# V_4.net
KiCad netlist of a schematic drawn in Altium Designer
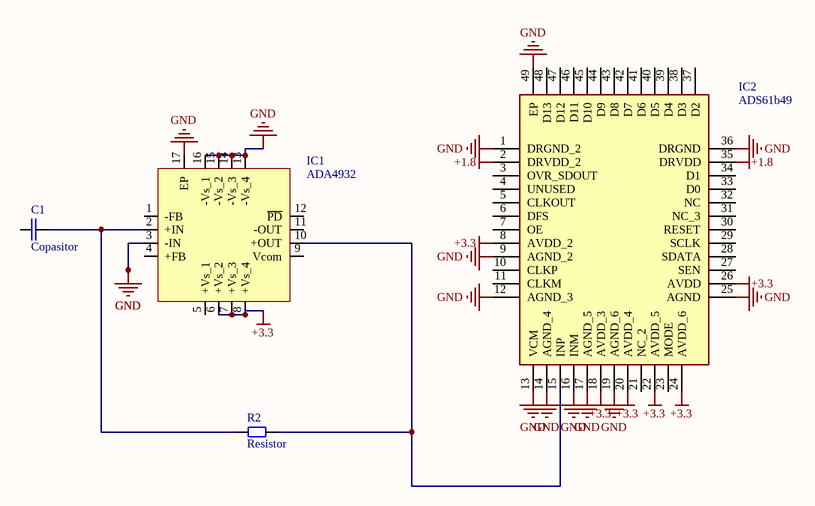
[diagram p0: V_4.SchDoc]

(export (version "E")
  (design (tool "Eeschema 10.0.6"))
  (components
    (comp (ref "C1") (value "Copasitor") (footprint "Copasitor") (libsource (lib "V_2") (part "Copasitor")))
    (comp (ref "IC1") (value "ADA4932") (footprint "ADA4932") (libsource (lib "V_2") (part "ADA4932")))
    (comp (ref "IC2") (value "ADS61b49") (footprint "ADS61b49") (libsource (lib "V__6") (part "ADS61b49")))
    (comp (ref "R2") (value "Resistor") (footprint "Resistor") (libsource (lib "V_2") (part "Resistor")))
  )
  (nets
    (net (code "1") (name "+1.8") (class "Default")
      (node (ref "IC2") (pin "2") (pinfunction "DRVDD_2_2") (pintype "passive"))
      (node (ref "IC2") (pin "35") (pinfunction "DRVDD_35") (pintype "passive"))
    )
    (net (code "2") (name "+3.3") (class "Default")
      (node (ref "IC1") (pin "6") (pinfunction "+Vs_2_6") (pintype "passive"))
      (node (ref "IC1") (pin "7") (pinfunction "+Vs_3_7") (pintype "passive"))
      (node (ref "IC1") (pin "8") (pinfunction "+Vs_4_8") (pintype "passive"))
      (node (ref "IC2") (pin "18") (pinfunction "AVDD_3_18") (pintype "passive"))
      (node (ref "IC2") (pin "20") (pinfunction "AVDD_4_20") (pintype "passive"))
      (node (ref "IC2") (pin "22") (pinfunction "AVDD_5_22") (pintype "passive"))
      (node (ref "IC2") (pin "24") (pinfunction "AVDD_6_24") (pintype "passive"))
      (node (ref "IC2") (pin "26") (pinfunction "AVDD_26") (pintype "passive"))
      (node (ref "IC2") (pin "8") (pinfunction "AVDD_2_8") (pintype "passive"))
    )
    (net (code "3") (name "GND") (class "Default")
      (node (ref "IC1") (pin "13") (pinfunction "-Vs_4_13") (pintype "passive"))
      (node (ref "IC1") (pin "14") (pinfunction "-Vs_3_14") (pintype "passive"))
      (node (ref "IC1") (pin "15") (pinfunction "-Vs_2_15") (pintype "passive"))
      (node (ref "IC1") (pin "16") (pinfunction "-Vs_1_16") (pintype "passive"))
      (node (ref "IC1") (pin "17") (pinfunction "EP_17") (pintype "passive"))
      (node (ref "IC1") (pin "3") (pinfunction "-IN_3") (pintype "passive"))
      (node (ref "IC2") (pin "1") (pinfunction "DRGND_2_1") (pintype "passive"))
      (node (ref "IC2") (pin "12") (pinfunction "AGND_3_12") (pintype "passive"))
      (node (ref "IC2") (pin "13") (pinfunction "VCM_13") (pintype "passive"))
      (node (ref "IC2") (pin "14") (pinfunction "AGND_4_14") (pintype "passive"))
      (node (ref "IC2") (pin "16") (pinfunction "INM_16") (pintype "passive"))
      (node (ref "IC2") (pin "17") (pinfunction "AGND_5_17") (pintype "passive"))
      (node (ref "IC2") (pin "19") (pinfunction "AGND_6_19") (pintype "passive"))
      (node (ref "IC2") (pin "25") (pinfunction "AGND_25") (pintype "passive"))
      (node (ref "IC2") (pin "36") (pinfunction "DRGND_36") (pintype "passive"))
      (node (ref "IC2") (pin "49") (pinfunction "EP_49") (pintype "passive"))
      (node (ref "IC2") (pin "9") (pinfunction "AGND_2_9") (pintype "passive"))
    )
    (net (code "4") (name "Net-(IC1-+IN)") (class "Default")
      (node (ref "C1") (pin "2") (pintype "passive"))
      (node (ref "IC1") (pin "2") (pinfunction "+IN_2") (pintype "passive"))
      (node (ref "R2") (pin "1") (pintype "passive"))
    )
    (net (code "5") (name "Net-(IC1-+OUT)") (class "Default")
      (node (ref "IC1") (pin "10") (pinfunction "+OUT_10") (pintype "passive"))
      (node (ref "IC2") (pin "15") (pinfunction "INP_15") (pintype "passive"))
      (node (ref "R2") (pin "2") (pintype "passive"))
    )
    (net (code "6") (name "unconnected-(C1-Pad1)") (class "Default")
      (node (ref "C1") (pin "1") (pintype "passive"))
    )
    (net (code "7") (name "unconnected-(IC1-+FB-Pad4)") (class "Default")
      (node (ref "IC1") (pin "4") (pinfunction "+FB_4") (pintype "passive"))
    )
    (net (code "8") (name "unconnected-(IC1-+Vs_1-Pad5)") (class "Default")
      (node (ref "IC1") (pin "5") (pinfunction "+Vs_1_5") (pintype "passive"))
    )
    (net (code "9") (name "unconnected-(IC1--FB-Pad1)") (class "Default")
      (node (ref "IC1") (pin "1") (pinfunction "-FB_1") (pintype "passive"))
    )
    (net (code "10") (name "unconnected-(IC1--OUT-Pad11)") (class "Default")
      (node (ref "IC1") (pin "11") (pinfunction "-OUT_11") (pintype "passive"))
    )
    (net (code "11") (name "unconnected-(IC1-Vcom-Pad9)") (class "Default")
      (node (ref "IC1") (pin "9") (pinfunction "Vcom_9") (pintype "passive"))
    )
    (net (code "12") (name "unconnected-(IC1-~{PD}-Pad12)") (class "Default")
      (node (ref "IC1") (pin "12") (pinfunction "~{PD}_12") (pintype "passive"))
    )
    (net (code "13") (name "unconnected-(IC2-CLKM-Pad11)") (class "Default")
      (node (ref "IC2") (pin "11") (pinfunction "CLKM_11") (pintype "passive"))
    )
    (net (code "14") (name "unconnected-(IC2-CLKOUT-Pad5)") (class "Default")
      (node (ref "IC2") (pin "5") (pinfunction "CLKOUT_5") (pintype "passive"))
    )
    (net (code "15") (name "unconnected-(IC2-CLKP-Pad10)") (class "Default")
      (node (ref "IC2") (pin "10") (pinfunction "CLKP_10") (pintype "passive"))
    )
    (net (code "16") (name "unconnected-(IC2-D0-Pad33)") (class "Default")
      (node (ref "IC2") (pin "33") (pinfunction "D0_33") (pintype "passive"))
    )
    (net (code "17") (name "unconnected-(IC2-D1-Pad34)") (class "Default")
      (node (ref "IC2") (pin "34") (pinfunction "D1_34") (pintype "passive"))
    )
    (net (code "18") (name "unconnected-(IC2-D2-Pad37)") (class "Default")
      (node (ref "IC2") (pin "37") (pinfunction "D2_37") (pintype "passive"))
    )
    (net (code "19") (name "unconnected-(IC2-D3-Pad38)") (class "Default")
      (node (ref "IC2") (pin "38") (pinfunction "D3_38") (pintype "passive"))
    )
    (net (code "20") (name "unconnected-(IC2-D4-Pad39)") (class "Default")
      (node (ref "IC2") (pin "39") (pinfunction "D4_39") (pintype "passive"))
    )
    (net (code "21") (name "unconnected-(IC2-D5-Pad40)") (class "Default")
      (node (ref "IC2") (pin "40") (pinfunction "D5_40") (pintype "passive"))
    )
    (net (code "22") (name "unconnected-(IC2-D6-Pad41)") (class "Default")
      (node (ref "IC2") (pin "41") (pinfunction "D6_41") (pintype "passive"))
    )
    (net (code "23") (name "unconnected-(IC2-D7-Pad42)") (class "Default")
      (node (ref "IC2") (pin "42") (pinfunction "D7_42") (pintype "passive"))
    )
    (net (code "24") (name "unconnected-(IC2-D8-Pad43)") (class "Default")
      (node (ref "IC2") (pin "43") (pinfunction "D8_43") (pintype "passive"))
    )
    (net (code "25") (name "unconnected-(IC2-D9-Pad44)") (class "Default")
      (node (ref "IC2") (pin "44") (pinfunction "D9_44") (pintype "passive"))
    )
    (net (code "26") (name "unconnected-(IC2-D10-Pad45)") (class "Default")
      (node (ref "IC2") (pin "45") (pinfunction "D10_45") (pintype "passive"))
    )
    (net (code "27") (name "unconnected-(IC2-D11-Pad46)") (class "Default")
      (node (ref "IC2") (pin "46") (pinfunction "D11_46") (pintype "passive"))
    )
    (net (code "28") (name "unconnected-(IC2-D12-Pad47)") (class "Default")
      (node (ref "IC2") (pin "47") (pinfunction "D12_47") (pintype "passive"))
    )
    (net (code "29") (name "unconnected-(IC2-D13-Pad48)") (class "Default")
      (node (ref "IC2") (pin "48") (pinfunction "D13_48") (pintype "passive"))
    )
    (net (code "30") (name "unconnected-(IC2-DFS-Pad6)") (class "Default")
      (node (ref "IC2") (pin "6") (pinfunction "DFS_6") (pintype "passive"))
    )
    (net (code "31") (name "unconnected-(IC2-MODE-Pad23)") (class "Default")
      (node (ref "IC2") (pin "23") (pinfunction "MODE_23") (pintype "passive"))
    )
    (net (code "32") (name "unconnected-(IC2-NC-Pad32)") (class "Default")
      (node (ref "IC2") (pin "32") (pinfunction "NC_32") (pintype "passive"))
    )
    (net (code "33") (name "unconnected-(IC2-NC_2-Pad21)") (class "Default")
      (node (ref "IC2") (pin "21") (pinfunction "NC_2_21") (pintype "passive"))
    )
    (net (code "34") (name "unconnected-(IC2-NC_3-Pad31)") (class "Default")
      (node (ref "IC2") (pin "31") (pinfunction "NC_3_31") (pintype "passive"))
    )
    (net (code "35") (name "unconnected-(IC2-OE-Pad7)") (class "Default")
      (node (ref "IC2") (pin "7") (pinfunction "OE_7") (pintype "passive"))
    )
    (net (code "36") (name "unconnected-(IC2-OVR_SDOUT-Pad3)") (class "Default")
      (node (ref "IC2") (pin "3") (pinfunction "OVR_SDOUT_3") (pintype "passive"))
    )
    (net (code "37") (name "unconnected-(IC2-RESET-Pad30)") (class "Default")
      (node (ref "IC2") (pin "30") (pinfunction "RESET_30") (pintype "passive"))
    )
    (net (code "38") (name "unconnected-(IC2-SCLK-Pad29)") (class "Default")
      (node (ref "IC2") (pin "29") (pinfunction "SCLK_29") (pintype "passive"))
    )
    (net (code "39") (name "unconnected-(IC2-SDATA-Pad28)") (class "Default")
      (node (ref "IC2") (pin "28") (pinfunction "SDATA_28") (pintype "passive"))
    )
    (net (code "40") (name "unconnected-(IC2-SEN-Pad27)") (class "Default")
      (node (ref "IC2") (pin "27") (pinfunction "SEN_27") (pintype "passive"))
    )
    (net (code "41") (name "unconnected-(IC2-UNUSED-Pad4)") (class "Default")
      (node (ref "IC2") (pin "4") (pinfunction "UNUSED_4") (pintype "passive"))
    )
  )
)
